# SAMD_Arduino_1.net
KiCad netlist of a schematic drawn in Altium Designer
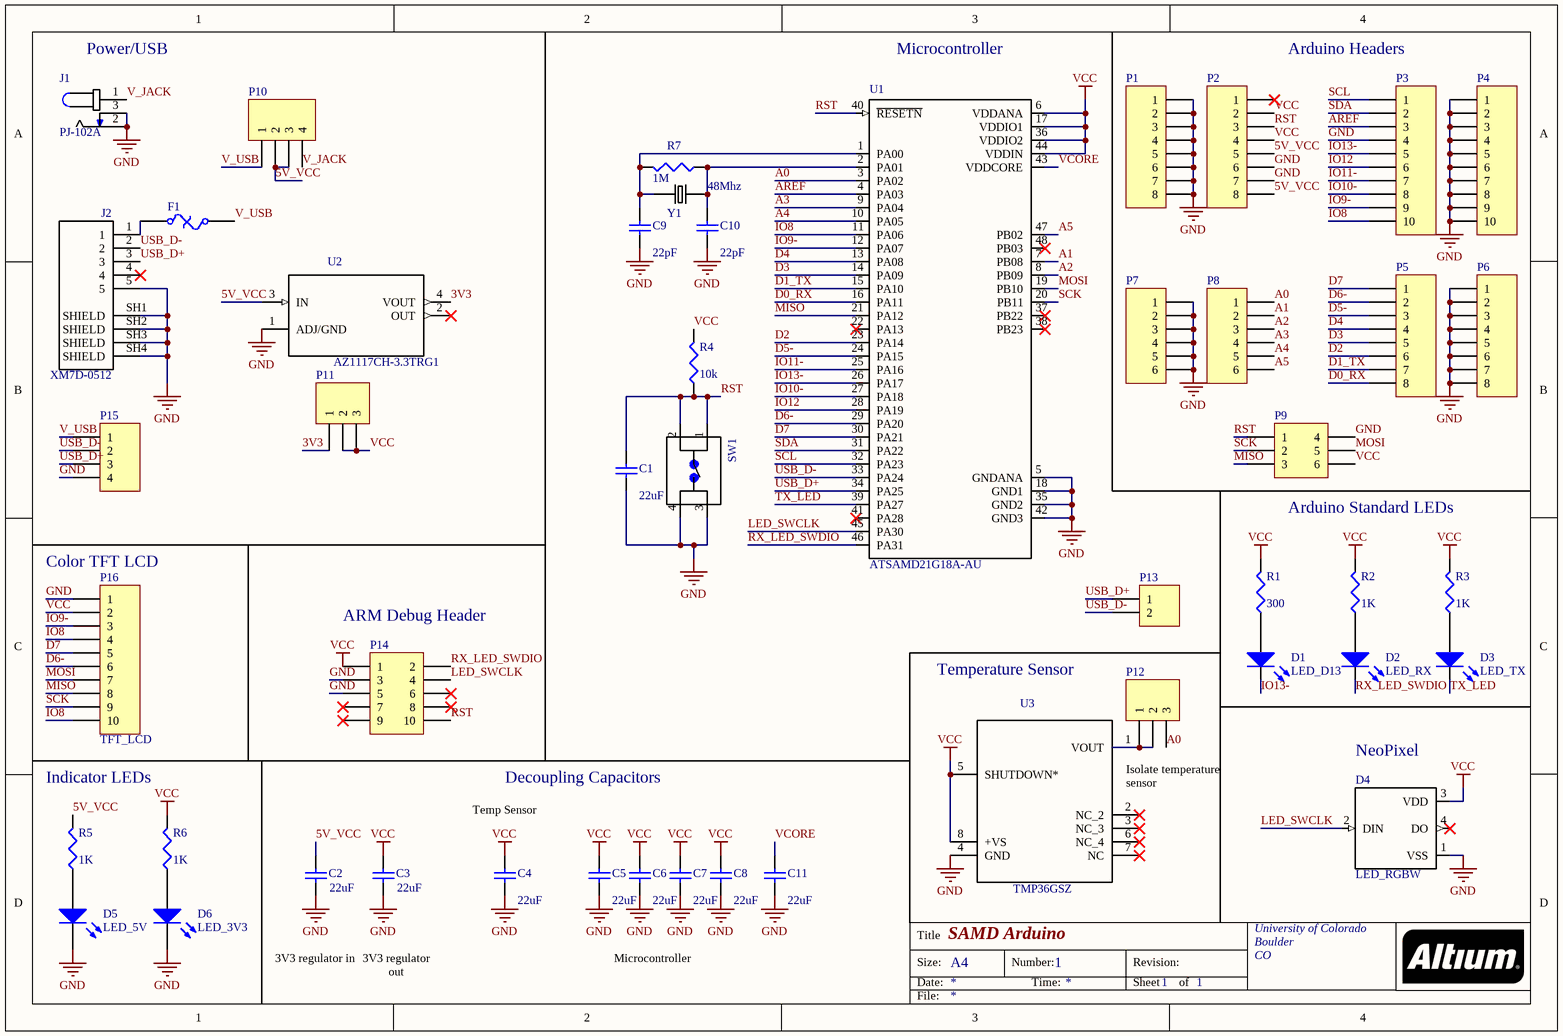
[diagram p0: SAMD_Arduino_1.SchDoc]

(export (version "E")
  (design (tool "Eeschema 10.0.6"))
  (components
    (comp (ref "C1")
      (value "22uF")
      (footprint "C1206")
      (description "Capacitor (Semiconductor SIM Model)")
      (fields (field (name "Comment") "Cap Semi") (field (name "PUBLISHER") "Altium Limited"))
      (libsource (lib "Miscellaneous Devices") (part "Cap Semi"))
    )
    (comp (ref "C2")
      (value "22uF")
      (footprint "C1206")
      (description "Capacitor (Semiconductor SIM Model)")
      (fields
        (field (name "DIGIKEYPARTNO") "1276-3300-1-ND")
        (field (name "Comment") "Cap Semi")
        (field (name "PUBLISHER") "Altium Limited")
      )
      (libsource (lib "Miscellaneous Devices") (part "Cap Semi"))
    )
    (comp (ref "C3")
      (value "22uF")
      (footprint "C1206")
      (description "Capacitor (Semiconductor SIM Model)")
      (fields
        (field (name "DIGIKEYPARTNO") "1276-3300-1-ND")
        (field (name "Comment") "Cap Semi")
        (field (name "PUBLISHER") "Altium Limited")
      )
      (libsource (lib "Miscellaneous Devices") (part "Cap Semi"))
    )
    (comp (ref "C4")
      (value "22uF")
      (footprint "C1206")
      (description "Capacitor (Semiconductor SIM Model)")
      (fields
        (field (name "DIGIKEYPARTNO") "1276-3300-1-ND")
        (field (name "Comment") "Cap Semi")
        (field (name "PUBLISHER") "Altium Limited")
      )
      (libsource (lib "Miscellaneous Devices") (part "Cap Semi"))
    )
    (comp (ref "C5")
      (value "22uF")
      (footprint "C1206")
      (description "Capacitor (Semiconductor SIM Model)")
      (fields
        (field (name "DIGIKEYPARTNO") "1276-3300-1-ND")
        (field (name "Comment") "Cap Semi")
        (field (name "PUBLISHER") "Altium Limited")
      )
      (libsource (lib "Miscellaneous Devices") (part "Cap Semi"))
    )
    (comp (ref "C6")
      (value "22uF")
      (footprint "C1206")
      (description "Capacitor (Semiconductor SIM Model)")
      (fields
        (field (name "DIGIKEYPARTNO") "1276-3300-1-ND")
        (field (name "Comment") "Cap Semi")
        (field (name "PUBLISHER") "Altium Limited")
      )
      (libsource (lib "Miscellaneous Devices") (part "Cap Semi"))
    )
    (comp (ref "C7")
      (value "22uF")
      (footprint "C1206")
      (description "Capacitor (Semiconductor SIM Model)")
      (fields
        (field (name "DIGIKEYPARTNO") "1276-3300-1-ND")
        (field (name "Comment") "Cap Semi")
        (field (name "PUBLISHER") "Altium Limited")
      )
      (libsource (lib "Miscellaneous Devices") (part "Cap Semi"))
    )
    (comp (ref "C8")
      (value "22uF")
      (footprint "C1206")
      (description "Capacitor (Semiconductor SIM Model)")
      (fields
        (field (name "DIGIKEYPARTNO") "1276-3300-1-ND")
        (field (name "Comment") "Cap Semi")
        (field (name "PUBLISHER") "Altium Limited")
      )
      (libsource (lib "Miscellaneous Devices") (part "Cap Semi"))
    )
    (comp (ref "C9")
      (value "22pF")
      (footprint "C1206")
      (description "Capacitor (Semiconductor SIM Model)")
      (fields
        (field (name "DIGIKEYPARTNO") "732-7867-1-ND")
        (field (name "Comment") "Cap Semi")
        (field (name "PUBLISHER") "Altium Limited")
      )
      (libsource (lib "Miscellaneous Devices") (part "Cap Semi"))
    )
    (comp (ref "C10")
      (value "22pF")
      (footprint "C1206")
      (description "Capacitor (Semiconductor SIM Model)")
      (fields
        (field (name "DIGIKEYPARTNO") "732-7867-1-ND")
        (field (name "Comment") "Cap Semi")
        (field (name "PUBLISHER") "Altium Limited")
      )
      (libsource (lib "Miscellaneous Devices") (part "Cap Semi"))
    )
    (comp (ref "C11")
      (value "22uF")
      (footprint "C1206")
      (description "Capacitor (Semiconductor SIM Model)")
      (fields
        (field (name "DIGIKEYPARTNO") "1276-3300-1-ND")
        (field (name "Comment") "Cap Semi")
        (field (name "PUBLISHER") "Altium Limited")
      )
      (libsource (lib "Miscellaneous Devices") (part "Cap Semi"))
    )
    (comp (ref "D1")
      (value "LED_D13")
      (footprint "3.2X1.6X1.1")
      (description "Typical RED, GREEN, YELLOW, AMBER GaAs LED")
      (fields (field (name "PUBLISHER") "Altium Limited"))
      (libsource (lib "Miscellaneous Devices") (part "LED2"))
    )
    (comp (ref "D2")
      (value "LED_RX")
      (footprint "3.2X1.6X1.1")
      (description "Typical RED, GREEN, YELLOW, AMBER GaAs LED")
      (fields (field (name "PUBLISHER") "Altium Limited"))
      (libsource (lib "Miscellaneous Devices") (part "LED2"))
    )
    (comp (ref "D3")
      (value "LED_TX")
      (footprint "3.2X1.6X1.1")
      (description "Typical RED, GREEN, YELLOW, AMBER GaAs LED")
      (fields (field (name "PUBLISHER") "Altium Limited"))
      (libsource (lib "Miscellaneous Devices") (part "LED2"))
    )
    (comp (ref "D4")
      (value "LED_RGBW")
      (footprint "*LED_IN-PI554FCH")
      (description "5050RGB with integrated IC built in 4 PIN Â•Viewing angle: 120 degrees")
      (fields (field (name "MP") "IN-PI554FCH") (field (name "MF") "Inolux"))
      (libsource (lib "IN-PI554FCH") (part "IN-PI554FCH"))
    )
    (comp (ref "D5")
      (value "LED_5V")
      (footprint "3.2X1.6X1.1")
      (description "Typical RED, GREEN, YELLOW, AMBER GaAs LED")
      (fields (field (name "PUBLISHER") "Altium Limited"))
      (libsource (lib "Miscellaneous Devices") (part "LED2"))
    )
    (comp (ref "D6")
      (value "LED_3V3")
      (footprint "3.2X1.6X1.1")
      (description "Typical RED, GREEN, YELLOW, AMBER GaAs LED")
      (fields (field (name "PUBLISHER") "Altium Limited"))
      (libsource (lib "Miscellaneous Devices") (part "LED2"))
    )
    (comp (ref "F1")
      (value "Fuse Thermal")
      (footprint "1812")
      (description "Thermal Fuse")
      (fields
        (field (name "MANUFACTURERPARTNO") "MF-MSMF050-2")
        (field (name "DIGIKEYPARTNO") "MF-MSMF050-2CT-ND")
        (field (name "PUBLISHER") "Altium Limited")
      )
      (libsource (lib "Miscellaneous Devices") (part "Fuse Thermal"))
    )
    (comp (ref "J1")
      (value "PJ-102A")
      (footprint "*CUI_PJ-102A")
      (description "2.0 mm Center Pin, 2.5 A, Right Angle, Through Hole, Tapered Pins, Dc Power Jack Connector")
      (fields (field (name "MF") "CUI Inc."))
      (libsource (lib "PJ-102A") (part "PJ-102A"))
    )
    (comp (ref "J2")
      (value "XM7D-0512")
      (footprint "*OMRON_XM7D-0512_XM7D-0512(Primary)")
      (description "Conn Mini USB Type B SKT 5 POS 0.8mm Solder RA Thru-Hole 5 Terminal 1 Port")
      (fields (field (name "MF") "Omron Electronics"))
      (libsource (lib "XM7D-0512") (part "XM7D-0512"))
    )
    (comp (ref "P1")
      (value "GND")
      (footprint "HDR1X8")
      (description "Header, 8-Pin")
      (fields (field (name "PUBLISHER") "Altium Limited"))
      (libsource (lib "") (part "Header 8_1"))
    )
    (comp (ref "P2")
      (value "P4")
      (footprint "HDR1X8")
      (description "Header, 8-Pin")
      (fields (field (name "PUBLISHER") "Altium Limited"))
      (libsource (lib "") (part "Header 8_1"))
    )
    (comp (ref "P3")
      (value "P1")
      (footprint "HDR1X10")
      (description "Header, 10-Pin")
      (fields (field (name "PUBLISHER") "Altium Limited"))
      (libsource (lib "Miscellaneous Connectors") (part "Header 10"))
    )
    (comp (ref "P4")
      (value "GND")
      (footprint "HDR1X10")
      (description "Header, 10-Pin")
      (fields (field (name "PUBLISHER") "Altium Limited"))
      (libsource (lib "Miscellaneous Connectors") (part "Header 10"))
    )
    (comp (ref "P5")
      (value "P2")
      (footprint "HDR1X8")
      (description "Header, 8-Pin")
      (fields (field (name "PUBLISHER") "Altium Limited"))
      (libsource (lib "Miscellaneous Connectors") (part "Header 8"))
    )
    (comp (ref "P6")
      (value "GND")
      (footprint "HDR1X8")
      (description "Header, 8-Pin")
      (fields (field (name "PUBLISHER") "Altium Limited"))
      (libsource (lib "Miscellaneous Connectors") (part "Header 8"))
    )
    (comp (ref "P7")
      (value "GND")
      (footprint "HDR1X6")
      (description "Header, 6-Pin")
      (fields (field (name "PUBLISHER") "Altium Limited"))
      (libsource (lib "Miscellaneous Connectors") (part "Header 6"))
    )
    (comp (ref "P8")
      (value "P3")
      (footprint "HDR1X6")
      (description "Header, 6-Pin")
      (fields (field (name "PUBLISHER") "Altium Limited"))
      (libsource (lib "Miscellaneous Connectors") (part "Header 6"))
    )
    (comp (ref "P9")
      (value "Header 3X2A")
      (footprint "HDR2X3_CEN")
      (description "Header, 3-Pin, Dual row")
      (fields (field (name "PUBLISHER") "Altium Limited"))
      (libsource (lib "Miscellaneous Connectors") (part "Header 3X2A"))
    )
    (comp (ref "P10")
      (value "Header 4")
      (footprint "HDR1X4")
      (description "Header, 4-Pin")
      (fields (field (name "PUBLISHER") "Altium Limited"))
      (libsource (lib "") (part "Header 4_1"))
    )
    (comp (ref "P11")
      (value "3.3 NC")
      (footprint "HDR1X3")
      (description "Header, 3-Pin")
      (fields (field (name "PUBLISHER") "Altium Limited"))
      (libsource (lib "Miscellaneous Connectors") (part "Header 3"))
    )
    (comp (ref "P12")
      (value "NC A0")
      (footprint "HDR1X3")
      (description "Header, 3-Pin")
      (fields (field (name "PUBLISHER") "Altium Limited"))
      (libsource (lib "Miscellaneous Connectors") (part "Header 3"))
    )
    (comp (ref "P13")
      (value "Header 2")
      (footprint "HDR1X2")
      (description "Header, 2-Pin")
      (fields (field (name "PUBLISHER") "Altium Limited"))
      (libsource (lib "Miscellaneous Connectors") (part "Header 2"))
    )
    (comp (ref "P14")
      (value "Header 5X2")
      (footprint "HDR2X5")
      (description "Header, 5-Pin, Dual row")
      (fields (field (name "PUBLISHER") "Altium Limited"))
      (libsource (lib "Miscellaneous Connectors") (part "Header 5X2"))
    )
    (comp (ref "P15")
      (value "Header 4")
      (footprint "HDR1X4")
      (description "Header, 4-Pin")
      (fields (field (name "PUBLISHER") "Altium Limited"))
      (libsource (lib "Miscellaneous Connectors") (part "Header 4"))
    )
    (comp (ref "P16")
      (value "TFT_LCD")
      (footprint "HDR1X10")
      (description "Header, 10-Pin")
      (fields (field (name "DIGIKEYPARTNO") "1212-1179-ND") (field (name "PUBLISHER") "Altium Limited"))
      (libsource (lib "Miscellaneous Connectors") (part "Header 10"))
    )
    (comp (ref "R1")
      (value "300")
      (footprint "C1206")
      (description "Resistor")
      (fields (field (name "Comment") "Res3") (field (name "PUBLISHER") "Altium Limited"))
      (libsource (lib "Miscellaneous Devices") (part "Res3"))
    )
    (comp (ref "R2")
      (value "1K")
      (footprint "C1206")
      (description "Resistor")
      (fields (field (name "Comment") "Res3") (field (name "PUBLISHER") "Altium Limited"))
      (libsource (lib "Miscellaneous Devices") (part "Res3"))
    )
    (comp (ref "R3")
      (value "1K")
      (footprint "C1206")
      (description "Resistor")
      (fields (field (name "Comment") "Res3") (field (name "PUBLISHER") "Altium Limited"))
      (libsource (lib "Miscellaneous Devices") (part "Res3"))
    )
    (comp (ref "R4")
      (value "10k")
      (footprint "C1206")
      (description "Resistor")
      (fields (field (name "Comment") "Res3") (field (name "PUBLISHER") "Altium Limited"))
      (libsource (lib "Miscellaneous Devices") (part "Res3"))
    )
    (comp (ref "R5")
      (value "1K")
      (footprint "C1206")
      (description "Resistor")
      (fields (field (name "Comment") "Res3") (field (name "PUBLISHER") "Altium Limited"))
      (libsource (lib "Miscellaneous Devices") (part "Res3"))
    )
    (comp (ref "R6")
      (value "1K")
      (footprint "C1206")
      (description "Resistor")
      (fields (field (name "Comment") "Res3") (field (name "PUBLISHER") "Altium Limited"))
      (libsource (lib "Miscellaneous Devices") (part "Res3"))
    )
    (comp (ref "R7")
      (value "1M")
      (footprint "C1206")
      (description "Resistor")
      (fields (field (name "Comment") "Res3") (field (name "PUBLISHER") "Altium Limited"))
      (libsource (lib "Miscellaneous Devices") (part "Res3"))
    )
    (comp (ref "SW1")
      (value "RESET")
      (footprint "*TE_FSM4JSMA")
      (description "FSM4JSMA=SMT,TACTILE,PB SWITCH")
      (fields (field (name "MF") "TE Connectivity") (field (name "MP") "FSM4JSMA"))
      (libsource (lib "FSM4JSMA") (part "FSM4JSMA"))
    )
    (comp (ref "U1")
      (value "ATSAMD21G18A-AU")
      (footprint "*QFP50P900X900X120-48N")
      (description "SAMD21G Series 256 kB Flash 32 kB SRAM 48 MHz 32-Bit Microcontroller - TQFP-48")
      (fields (field (name "MF") "Microchip"))
      (libsource (lib "ATSAMD21G18A-AU") (part "ATSAMD21G18A-AU"))
    )
    (comp (ref "U2")
      (value "AZ1117CH-3.3TRG1")
      (footprint "*SOT230P696X180-4N")
      (description "Voltage stabiliser; LDO, fixed; 3.3V; 0.8A; SOT223; SMD")
      (fields
        (field (name "MF") "Diodes Incorporated")
        (field (name "DIGIKEYPARTNO") "AZ1117CH-3.3TRG1DICT-ND")
      )
      (libsource (lib "LM1117MP-3.3") (part "LM1117MP-3.3"))
    )
    (comp (ref "U3")
      (value "TMP36GSZ")
      (footprint "*SOIC127P600X175-8N")
      (description "Temp Sensor Analog_Voltage_ Serial _2-Wire_ 8-Pin SOIC N Tube")
      (fields (field (name "MF") "Analog Devices"))
      (libsource (lib "TMP36GSZ") (part "TMP36GSZ"))
    )
    (comp (ref "Y1")
      (value "48Mhz")
      (footprint "*XTAL_ECS-35-17-5PX-TR")
      (description "Crystal 3.579545MHz Â±30ppm _Tol_ Â±50ppm _Stability_ 17pF FUND 150Ohm 2-Pin HC-49/USX SMD T/R")
      (fields (field (name "MF") "Abracon LLC") (field (name "MP") "ABLS-48.000MHZ-B2-T"))
      (libsource (lib "ECS-35-17-5PX-TR") (part "ECS-35-17-5PX-TR"))
    )
  )
  (nets
    (net (code "1") (name "/3V3") (class "Default")
      (node (ref "P11") (pin "1") (pinfunction "1_1") (pintype "passive"))
      (node (ref "U2") (pin "4") (pinfunction "VOUT_4") (pintype "output"))
    )
    (net (code "2") (name "/5V_VCC") (class "Default")
      (node (ref "C2") (pin "2") (pinfunction "2_2") (pintype "passive"))
      (node (ref "P10") (pin "2") (pinfunction "2_2") (pintype "passive"))
      (node (ref "P10") (pin "3") (pinfunction "3_3") (pintype "passive"))
      (node (ref "P2") (pin "5") (pinfunction "5_5") (pintype "passive"))
      (node (ref "P2") (pin "8") (pinfunction "8_8") (pintype "passive"))
      (node (ref "R5") (pin "2") (pinfunction "2_2") (pintype "passive"))
      (node (ref "U2") (pin "3") (pinfunction "IN_3") (pintype "input"))
    )
    (net (code "3") (name "/A0") (class "Default")
      (node (ref "P12") (pin "3") (pinfunction "3_3") (pintype "passive"))
      (node (ref "P8") (pin "1") (pinfunction "1_1") (pintype "passive"))
      (node (ref "U1") (pin "3") (pinfunction "PA02_3") (pintype "bidirectional"))
    )
    (net (code "4") (name "/A1") (class "Default")
      (node (ref "P8") (pin "2") (pinfunction "2_2") (pintype "passive"))
      (node (ref "U1") (pin "7") (pinfunction "PB08_7") (pintype "bidirectional"))
    )
    (net (code "5") (name "/A2") (class "Default")
      (node (ref "P8") (pin "3") (pinfunction "3_3") (pintype "passive"))
      (node (ref "U1") (pin "8") (pinfunction "PB09_8") (pintype "bidirectional"))
    )
    (net (code "6") (name "/A3") (class "Default")
      (node (ref "P8") (pin "4") (pinfunction "4_4") (pintype "passive"))
      (node (ref "U1") (pin "9") (pinfunction "PA04_9") (pintype "bidirectional"))
    )
    (net (code "7") (name "/A4") (class "Default")
      (node (ref "P8") (pin "5") (pinfunction "5_5") (pintype "passive"))
      (node (ref "U1") (pin "10") (pinfunction "PA05_10") (pintype "bidirectional"))
    )
    (net (code "8") (name "/A5") (class "Default")
      (node (ref "P8") (pin "6") (pinfunction "6_6") (pintype "passive"))
      (node (ref "U1") (pin "47") (pinfunction "PB02_47") (pintype "bidirectional"))
    )
    (net (code "9") (name "/AREF") (class "Default")
      (node (ref "P3") (pin "3") (pinfunction "3_3") (pintype "passive"))
      (node (ref "U1") (pin "4") (pinfunction "PA03_4") (pintype "bidirectional"))
    )
    (net (code "10") (name "/D0_RX") (class "Default")
      (node (ref "P5") (pin "8") (pinfunction "8_8") (pintype "passive"))
      (node (ref "U1") (pin "16") (pinfunction "PA11_16") (pintype "bidirectional"))
    )
    (net (code "11") (name "/D1_TX") (class "Default")
      (node (ref "P5") (pin "7") (pinfunction "7_7") (pintype "passive"))
      (node (ref "U1") (pin "15") (pinfunction "PA10_15") (pintype "bidirectional"))
    )
    (net (code "12") (name "/D2") (class "Default")
      (node (ref "P5") (pin "6") (pinfunction "6_6") (pintype "passive"))
      (node (ref "U1") (pin "23") (pinfunction "PA14_23") (pintype "bidirectional"))
    )
    (net (code "13") (name "/D3") (class "Default")
      (node (ref "P5") (pin "5") (pinfunction "5_5") (pintype "passive"))
      (node (ref "U1") (pin "14") (pinfunction "PA09_14") (pintype "bidirectional"))
    )
    (net (code "14") (name "/D4") (class "Default")
      (node (ref "P5") (pin "4") (pinfunction "4_4") (pintype "passive"))
      (node (ref "U1") (pin "13") (pinfunction "PA08_13") (pintype "bidirectional"))
    )
    (net (code "15") (name "/D5-") (class "Default")
      (node (ref "P5") (pin "3") (pinfunction "3_3") (pintype "passive"))
      (node (ref "U1") (pin "24") (pinfunction "PA15_24") (pintype "bidirectional"))
    )
    (net (code "16") (name "/D6-") (class "Default")
      (node (ref "P16") (pin "6") (pinfunction "6_6") (pintype "passive"))
      (node (ref "P5") (pin "2") (pinfunction "2_2") (pintype "passive"))
      (node (ref "U1") (pin "29") (pinfunction "PA20_29") (pintype "bidirectional"))
    )
    (net (code "17") (name "/D7") (class "Default")
      (node (ref "P16") (pin "5") (pinfunction "5_5") (pintype "passive"))
      (node (ref "P5") (pin "1") (pinfunction "1_1") (pintype "passive"))
      (node (ref "U1") (pin "30") (pinfunction "PA21_30") (pintype "bidirectional"))
    )
    (net (code "18") (name "/IO8") (class "Default")
      (node (ref "P16") (pin "10") (pinfunction "10_10") (pintype "passive"))
      (node (ref "P16") (pin "4") (pinfunction "4_4") (pintype "passive"))
      (node (ref "P3") (pin "10") (pinfunction "10_10") (pintype "passive"))
      (node (ref "U1") (pin "11") (pinfunction "PA06_11") (pintype "bidirectional"))
    )
    (net (code "19") (name "/IO9-") (class "Default")
      (node (ref "P16") (pin "3") (pinfunction "3_3") (pintype "passive"))
      (node (ref "P3") (pin "9") (pinfunction "9_9") (pintype "passive"))
      (node (ref "U1") (pin "12") (pinfunction "PA07_12") (pintype "bidirectional"))
    )
    (net (code "20") (name "/IO10-") (class "Default")
      (node (ref "P3") (pin "8") (pinfunction "8_8") (pintype "passive"))
      (node (ref "U1") (pin "27") (pinfunction "PA18_27") (pintype "bidirectional"))
    )
    (net (code "21") (name "/IO11-") (class "Default")
      (node (ref "P3") (pin "7") (pinfunction "7_7") (pintype "passive"))
      (node (ref "U1") (pin "25") (pinfunction "PA16_25") (pintype "bidirectional"))
    )
    (net (code "22") (name "/IO12") (class "Default")
      (node (ref "P3") (pin "6") (pinfunction "6_6") (pintype "passive"))
      (node (ref "U1") (pin "28") (pinfunction "PA19_28") (pintype "bidirectional"))
    )
    (net (code "23") (name "/IO13-") (class "Default")
      (node (ref "D1") (pin "2") (pinfunction "K_2") (pintype "passive"))
      (node (ref "P3") (pin "5") (pinfunction "5_5") (pintype "passive"))
      (node (ref "U1") (pin "26") (pinfunction "PA17_26") (pintype "bidirectional"))
    )
    (net (code "24") (name "/LED_SWCLK") (class "Default")
      (node (ref "D4") (pin "2") (pinfunction "DIN_2") (pintype "input"))
      (node (ref "P14") (pin "4") (pinfunction "4_4") (pintype "passive"))
      (node (ref "U1") (pin "45") (pinfunction "PA30_45") (pintype "bidirectional"))
    )
    (net (code "25") (name "/MISO") (class "Default")
      (node (ref "P16") (pin "8") (pinfunction "8_8") (pintype "passive"))
      (node (ref "P9") (pin "3") (pinfunction "3_3") (pintype "passive"))
      (node (ref "U1") (pin "21") (pinfunction "PA12_21") (pintype "bidirectional"))
    )
    (net (code "26") (name "/MOSI") (class "Default")
      (node (ref "P16") (pin "7") (pinfunction "7_7") (pintype "passive"))
      (node (ref "P9") (pin "5") (pinfunction "5_5") (pintype "passive"))
      (node (ref "U1") (pin "19") (pinfunction "PB10_19") (pintype "bidirectional"))
    )
    (net (code "27") (name "/RST") (class "Default")
      (node (ref "C1") (pin "2") (pinfunction "2_2") (pintype "passive"))
      (node (ref "P14") (pin "10") (pinfunction "10_10") (pintype "passive"))
      (node (ref "P2") (pin "3") (pinfunction "3_3") (pintype "passive"))
      (node (ref "P9") (pin "1") (pinfunction "1_1") (pintype "passive"))
      (node (ref "R4") (pin "1") (pinfunction "1_1") (pintype "passive"))
      (node (ref "SW1") (pin "1") (pinfunction "1_1") (pintype "passive"))
      (node (ref "SW1") (pin "2") (pinfunction "2_2") (pintype "passive"))
      (node (ref "U1") (pin "40") (pinfunction "~{RESETN}_40") (pintype "input"))
    )
    (net (code "28") (name "/RX_LED_SWDIO") (class "Default")
      (node (ref "D2") (pin "2") (pinfunction "K_2") (pintype "passive"))
      (node (ref "P14") (pin "2") (pinfunction "2_2") (pintype "passive"))
      (node (ref "U1") (pin "46") (pinfunction "PA31_46") (pintype "bidirectional"))
    )
    (net (code "29") (name "/SCK") (class "Default")
      (node (ref "P16") (pin "9") (pinfunction "9_9") (pintype "passive"))
      (node (ref "P9") (pin "2") (pinfunction "2_2") (pintype "passive"))
      (node (ref "U1") (pin "20") (pinfunction "PB11_20") (pintype "bidirectional"))
    )
    (net (code "30") (name "/SCL") (class "Default")
      (node (ref "P3") (pin "1") (pinfunction "1_1") (pintype "passive"))
      (node (ref "U1") (pin "32") (pinfunction "PA23_32") (pintype "bidirectional"))
    )
    (net (code "31") (name "/SDA") (class "Default")
      (node (ref "P3") (pin "2") (pinfunction "2_2") (pintype "passive"))
      (node (ref "U1") (pin "31") (pinfunction "PA22_31") (pintype "bidirectional"))
    )
    (net (code "32") (name "/TX_LED") (class "Default")
      (node (ref "D3") (pin "2") (pinfunction "K_2") (pintype "passive"))
      (node (ref "U1") (pin "39") (pinfunction "PA27_39") (pintype "bidirectional"))
    )
    (net (code "33") (name "/USB_D+") (class "Default")
      (node (ref "J2") (pin "3") (pinfunction "3_3") (pintype "passive"))
      (node (ref "P13") (pin "1") (pinfunction "1_1") (pintype "passive"))
      (node (ref "P15") (pin "3") (pinfunction "3_3") (pintype "passive"))
      (node (ref "U1") (pin "34") (pinfunction "PA25_34") (pintype "bidirectional"))
    )
    (net (code "34") (name "/USB_D-") (class "Default")
      (node (ref "J2") (pin "2") (pinfunction "2_2") (pintype "passive"))
      (node (ref "P13") (pin "2") (pinfunction "2_2") (pintype "passive"))
      (node (ref "P15") (pin "2") (pinfunction "2_2") (pintype "passive"))
      (node (ref "U1") (pin "33") (pinfunction "PA24_33") (pintype "bidirectional"))
    )
    (net (code "35") (name "/VCORE") (class "Default")
      (node (ref "C11") (pin "2") (pinfunction "2_2") (pintype "passive"))
      (node (ref "U1") (pin "43") (pinfunction "VDDCORE_43") (pintype "power_in"))
    )
    (net (code "36") (name "/V_JACK") (class "Default")
      (node (ref "J1") (pin "1") (pinfunction "1_1") (pintype "passive"))
      (node (ref "P10") (pin "4") (pinfunction "4_4") (pintype "passive"))
    )
    (net (code "37") (name "/V_USB") (class "Default")
      (node (ref "F1") (pin "2") (pinfunction "2_2") (pintype "passive"))
      (node (ref "P10") (pin "1") (pinfunction "1_1") (pintype "passive"))
      (node (ref "P15") (pin "1") (pinfunction "1_1") (pintype "passive"))
    )
    (net (code "38") (name "GND") (class "Default")
      (node (ref "C1") (pin "1") (pinfunction "1_1") (pintype "passive"))
      (node (ref "C10") (pin "1") (pinfunction "1_1") (pintype "passive"))
      (node (ref "C11") (pin "1") (pinfunction "1_1") (pintype "passive"))
      (node (ref "C2") (pin "1") (pinfunction "1_1") (pintype "passive"))
      (node (ref "C3") (pin "1") (pinfunction "1_1") (pintype "passive"))
      (node (ref "C4") (pin "1") (pinfunction "1_1") (pintype "passive"))
      (node (ref "C5") (pin "1") (pinfunction "1_1") (pintype "passive"))
      (node (ref "C6") (pin "1") (pinfunction "1_1") (pintype "passive"))
      (node (ref "C7") (pin "1") (pinfunction "1_1") (pintype "passive"))
      (node (ref "C8") (pin "1") (pinfunction "1_1") (pintype "passive"))
      (node (ref "C9") (pin "1") (pinfunction "1_1") (pintype "passive"))
      (node (ref "D4") (pin "1") (pinfunction "VSS_1") (pintype "power_in"))
      (node (ref "D5") (pin "2") (pinfunction "K_2") (pintype "passive"))
      (node (ref "D6") (pin "2") (pinfunction "K_2") (pintype "passive"))
      (node (ref "J1") (pin "2") (pinfunction "2_2") (pintype "passive"))
      (node (ref "J1") (pin "3") (pinfunction "3_3") (pintype "passive"))
      (node (ref "J2") (pin "5") (pinfunction "5_5") (pintype "passive"))
      (node (ref "J2") (pin "SH1") (pinfunction "SHIELD_SH1") (pintype "passive"))
      (node (ref "J2") (pin "SH2") (pinfunction "SHIELD_SH2") (pintype "passive"))
      (node (ref "J2") (pin "SH3") (pinfunction "SHIELD_SH3") (pintype "passive"))
      (node (ref "J2") (pin "SH4") (pinfunction "SHIELD_SH4") (pintype "passive"))
      (node (ref "P1") (pin "1") (pinfunction "1_1") (pintype "passive"))
      (node (ref "P1") (pin "2") (pinfunction "2_2") (pintype "passive"))
      (node (ref "P1") (pin "3") (pinfunction "3_3") (pintype "passive"))
      (node (ref "P1") (pin "4") (pinfunction "4_4") (pintype "passive"))
      (node (ref "P1") (pin "5") (pinfunction "5_5") (pintype "passive"))
      (node (ref "P1") (pin "6") (pinfunction "6_6") (pintype "passive"))
      (node (ref "P1") (pin "7") (pinfunction "7_7") (pintype "passive"))
      (node (ref "P1") (pin "8") (pinfunction "8_8") (pintype "passive"))
      (node (ref "P14") (pin "3") (pinfunction "3_3") (pintype "passive"))
      (node (ref "P14") (pin "5") (pinfunction "5_5") (pintype "passive"))
      (node (ref "P15") (pin "4") (pinfunction "4_4") (pintype "passive"))
      (node (ref "P16") (pin "1") (pinfunction "1_1") (pintype "passive"))
      (node (ref "P2") (pin "6") (pinfunction "6_6") (pintype "passive"))
      (node (ref "P2") (pin "7") (pinfunction "7_7") (pintype "passive"))
      (node (ref "P3") (pin "4") (pinfunction "4_4") (pintype "passive"))
      (node (ref "P4") (pin "1") (pinfunction "1_1") (pintype "passive"))
      (node (ref "P4") (pin "10") (pinfunction "10_10") (pintype "passive"))
      (node (ref "P4") (pin "2") (pinfunction "2_2") (pintype "passive"))
      (node (ref "P4") (pin "3") (pinfunction "3_3") (pintype "passive"))
      (node (ref "P4") (pin "4") (pinfunction "4_4") (pintype "passive"))
      (node (ref "P4") (pin "5") (pinfunction "5_5") (pintype "passive"))
      (node (ref "P4") (pin "6") (pinfunction "6_6") (pintype "passive"))
      (node (ref "P4") (pin "7") (pinfunction "7_7") (pintype "passive"))
      (node (ref "P4") (pin "8") (pinfunction "8_8") (pintype "passive"))
      (node (ref "P4") (pin "9") (pinfunction "9_9") (pintype "passive"))
      (node (ref "P6") (pin "1") (pinfunction "1_1") (pintype "passive"))
      (node (ref "P6") (pin "2") (pinfunction "2_2") (pintype "passive"))
      (node (ref "P6") (pin "3") (pinfunction "3_3") (pintype "passive"))
      (node (ref "P6") (pin "4") (pinfunction "4_4") (pintype "passive"))
      (node (ref "P6") (pin "5") (pinfunction "5_5") (pintype "passive"))
      (node (ref "P6") (pin "6") (pinfunction "6_6") (pintype "passive"))
      (node (ref "P6") (pin "7") (pinfunction "7_7") (pintype "passive"))
      (node (ref "P6") (pin "8") (pinfunction "8_8") (pintype "passive"))
      (node (ref "P7") (pin "1") (pinfunction "1_1") (pintype "passive"))
      (node (ref "P7") (pin "2") (pinfunction "2_2") (pintype "passive"))
      (node (ref "P7") (pin "3") (pinfunction "3_3") (pintype "passive"))
      (node (ref "P7") (pin "4") (pinfunction "4_4") (pintype "passive"))
      (node (ref "P7") (pin "5") (pinfunction "5_5") (pintype "passive"))
      (node (ref "P7") (pin "6") (pinfunction "6_6") (pintype "passive"))
      (node (ref "P9") (pin "4") (pinfunction "4_4") (pintype "passive"))
      (node (ref "SW1") (pin "3") (pinfunction "3_3") (pintype "passive"))
      (node (ref "SW1") (pin "4") (pinfunction "4_4") (pintype "passive"))
      (node (ref "U1") (pin "18") (pinfunction "GND1_18") (pintype "power_in"))
      (node (ref "U1") (pin "35") (pinfunction "GND2_35") (pintype "power_in"))
      (node (ref "U1") (pin "42") (pinfunction "GND3_42") (pintype "power_in"))
      (node (ref "U1") (pin "5") (pinfunction "GNDANA_5") (pintype "power_in"))
      (node (ref "U2") (pin "1") (pinfunction "ADJ/GND_1") (pintype "passive"))
      (node (ref "U3") (pin "4") (pinfunction "GND_4") (pintype "passive"))
    )
    (net (code "39") (name "Net-(D1-A)") (class "Default")
      (node (ref "D1") (pin "1") (pinfunction "A_1") (pintype "passive"))
      (node (ref "R1") (pin "1") (pinfunction "1_1") (pintype "passive"))
    )
    (net (code "40") (name "Net-(D2-A)") (class "Default")
      (node (ref "D2") (pin "1") (pinfunction "A_1") (pintype "passive"))
      (node (ref "R2") (pin "1") (pinfunction "1_1") (pintype "passive"))
    )
    (net (code "41") (name "Net-(D3-A)") (class "Default")
      (node (ref "D3") (pin "1") (pinfunction "A_1") (pintype "passive"))
      (node (ref "R3") (pin "1") (pinfunction "1_1") (pintype "passive"))
    )
    (net (code "42") (name "Net-(D5-A)") (class "Default")
      (node (ref "D5") (pin "1") (pinfunction "A_1") (pintype "passive"))
      (node (ref "R5") (pin "1") (pinfunction "1_1") (pintype "passive"))
    )
    (net (code "43") (name "Net-(D6-A)") (class "Default")
      (node (ref "D6") (pin "1") (pinfunction "A_1") (pintype "passive"))
      (node (ref "R6") (pin "1") (pinfunction "1_1") (pintype "passive"))
    )
    (net (code "44") (name "Net-(F1-Pad1)") (class "Default")
      (node (ref "F1") (pin "1") (pinfunction "1_1") (pintype "passive"))
      (node (ref "J2") (pin "1") (pinfunction "1_1") (pintype "passive"))
    )
    (net (code "45") (name "Net-(U1-PA00)") (class "Default")
      (node (ref "C9") (pin "2") (pinfunction "2_2") (pintype "passive"))
      (node (ref "R7") (pin "2") (pinfunction "2_2") (pintype "passive"))
      (node (ref "U1") (pin "1") (pinfunction "PA00_1") (pintype "bidirectional"))
      (node (ref "Y1") (pin "1") (pinfunction "1_1") (pintype "passive"))
    )
    (net (code "46") (name "Net-(U1-PA01)") (class "Default")
      (node (ref "C10") (pin "2") (pinfunction "2_2") (pintype "passive"))
      (node (ref "R7") (pin "1") (pinfunction "1_1") (pintype "passive"))
      (node (ref "U1") (pin "2") (pinfunction "PA01_2") (pintype "bidirectional"))
      (node (ref "Y1") (pin "2") (pinfunction "2_2") (pintype "passive"))
    )
    (net (code "47") (name "Net-(U3-VOUT)") (class "Default")
      (node (ref "P12") (pin "1") (pinfunction "1_1") (pintype "passive"))
      (node (ref "P12") (pin "2") (pinfunction "2_2") (pintype "passive"))
      (node (ref "U3") (pin "1") (pinfunction "VOUT_1") (pintype "passive"))
    )
    (net (code "48") (name "VCC") (class "Default")
      (node (ref "C3") (pin "2") (pinfunction "2_2") (pintype "passive"))
      (node (ref "C4") (pin "2") (pinfunction "2_2") (pintype "passive"))
      (node (ref "C5") (pin "2") (pinfunction "2_2") (pintype "passive"))
      (node (ref "C6") (pin "2") (pinfunction "2_2") (pintype "passive"))
      (node (ref "C7") (pin "2") (pinfunction "2_2") (pintype "passive"))
      (node (ref "C8") (pin "2") (pinfunction "2_2") (pintype "passive"))
      (node (ref "D4") (pin "3") (pinfunction "VDD_3") (pintype "power_in"))
      (node (ref "P11") (pin "2") (pinfunction "2_2") (pintype "passive"))
      (node (ref "P11") (pin "3") (pinfunction "3_3") (pintype "passive"))
      (node (ref "P14") (pin "1") (pinfunction "1_1") (pintype "passive"))
      (node (ref "P16") (pin "2") (pinfunction "2_2") (pintype "passive"))
      (node (ref "P2") (pin "2") (pinfunction "2_2") (pintype "passive"))
      (node (ref "P2") (pin "4") (pinfunction "4_4") (pintype "passive"))
      (node (ref "P9") (pin "6") (pinfunction "6_6") (pintype "passive"))
      (node (ref "R1") (pin "2") (pinfunction "2_2") (pintype "passive"))
      (node (ref "R2") (pin "2") (pinfunction "2_2") (pintype "passive"))
      (node (ref "R3") (pin "2") (pinfunction "2_2") (pintype "passive"))
      (node (ref "R4") (pin "2") (pinfunction "2_2") (pintype "passive"))
      (node (ref "R6") (pin "2") (pinfunction "2_2") (pintype "passive"))
      (node (ref "U1") (pin "17") (pinfunction "VDDIO1_17") (pintype "power_in"))
      (node (ref "U1") (pin "36") (pinfunction "VDDIO2_36") (pintype "power_in"))
      (node (ref "U1") (pin "44") (pinfunction "VDDIN_44") (pintype "power_in"))
      (node (ref "U1") (pin "6") (pinfunction "VDDANA_6") (pintype "power_in"))
      (node (ref "U3") (pin "5") (pinfunction "SHUTDOWN*_5") (pintype "passive"))
      (node (ref "U3") (pin "8") (pinfunction "+VS_8") (pintype "power_in"))
    )
    (net (code "49") (name "unconnected-(D4-DO-Pad4)") (class "Default")
      (node (ref "D4") (pin "4") (pinfunction "DO_4") (pintype "output+no_connect"))
    )
    (net (code "50") (name "unconnected-(J2-Pad4)") (class "Default")
      (node (ref "J2") (pin "4") (pinfunction "4_4") (pintype "passive+no_connect"))
    )
    (net (code "51") (name "unconnected-(P2-Pad1)") (class "Default")
      (node (ref "P2") (pin "1") (pinfunction "1_1") (pintype "passive+no_connect"))
    )
    (net (code "52") (name "unconnected-(P14-Pad6)") (class "Default")
      (node (ref "P14") (pin "6") (pinfunction "6_6") (pintype "passive+no_connect"))
    )
    (net (code "53") (name "unconnected-(P14-Pad7)") (class "Default")
      (node (ref "P14") (pin "7") (pinfunction "7_7") (pintype "passive+no_connect"))
    )
    (net (code "54") (name "unconnected-(P14-Pad8)") (class "Default")
      (node (ref "P14") (pin "8") (pinfunction "8_8") (pintype "passive+no_connect"))
    )
    (net (code "55") (name "unconnected-(P14-Pad9)") (class "Default")
      (node (ref "P14") (pin "9") (pinfunction "9_9") (pintype "passive+no_connect"))
    )
    (net (code "56") (name "unconnected-(U1-PA13-Pad22)") (class "Default")
      (node (ref "U1") (pin "22") (pinfunction "PA13_22") (pintype "bidirectional+no_connect"))
    )
    (net (code "57") (name "unconnected-(U1-PA28-Pad41)") (class "Default")
      (node (ref "U1") (pin "41") (pinfunction "PA28_41") (pintype "bidirectional+no_connect"))
    )
    (net (code "58") (name "unconnected-(U1-PB03-Pad48)") (class "Default")
      (node (ref "U1") (pin "48") (pinfunction "PB03_48") (pintype "bidirectional+no_connect"))
    )
    (net (code "59") (name "unconnected-(U1-PB22-Pad37)") (class "Default")
      (node (ref "U1") (pin "37") (pinfunction "PB22_37") (pintype "bidirectional+no_connect"))
    )
    (net (code "60") (name "unconnected-(U1-PB23-Pad38)") (class "Default")
      (node (ref "U1") (pin "38") (pinfunction "PB23_38") (pintype "bidirectional+no_connect"))
    )
    (net (code "61") (name "unconnected-(U2-OUT-Pad2)") (class "Default")
      (node (ref "U2") (pin "2") (pinfunction "OUT_2") (pintype "output+no_connect"))
    )
    (net (code "62") (name "unconnected-(U3-NC-Pad7)") (class "Default")
      (node (ref "U3") (pin "7") (pinfunction "NC_7") (pintype "passive+no_connect"))
    )
    (net (code "63") (name "unconnected-(U3-NC_2-Pad2)") (class "Default")
      (node (ref "U3") (pin "2") (pinfunction "NC_2_2") (pintype "passive+no_connect"))
    )
    (net (code "64") (name "unconnected-(U3-NC_3-Pad3)") (class "Default")
      (node (ref "U3") (pin "3") (pinfunction "NC_3_3") (pintype "passive+no_connect"))
    )
    (net (code "65") (name "unconnected-(U3-NC_4-Pad6)") (class "Default")
      (node (ref "U3") (pin "6") (pinfunction "NC_4_6") (pintype "passive+no_connect"))
    )
  )
)
